# Arduino-Pro-Mini.net
KiCad netlist of a schematic drawn in EAGLE
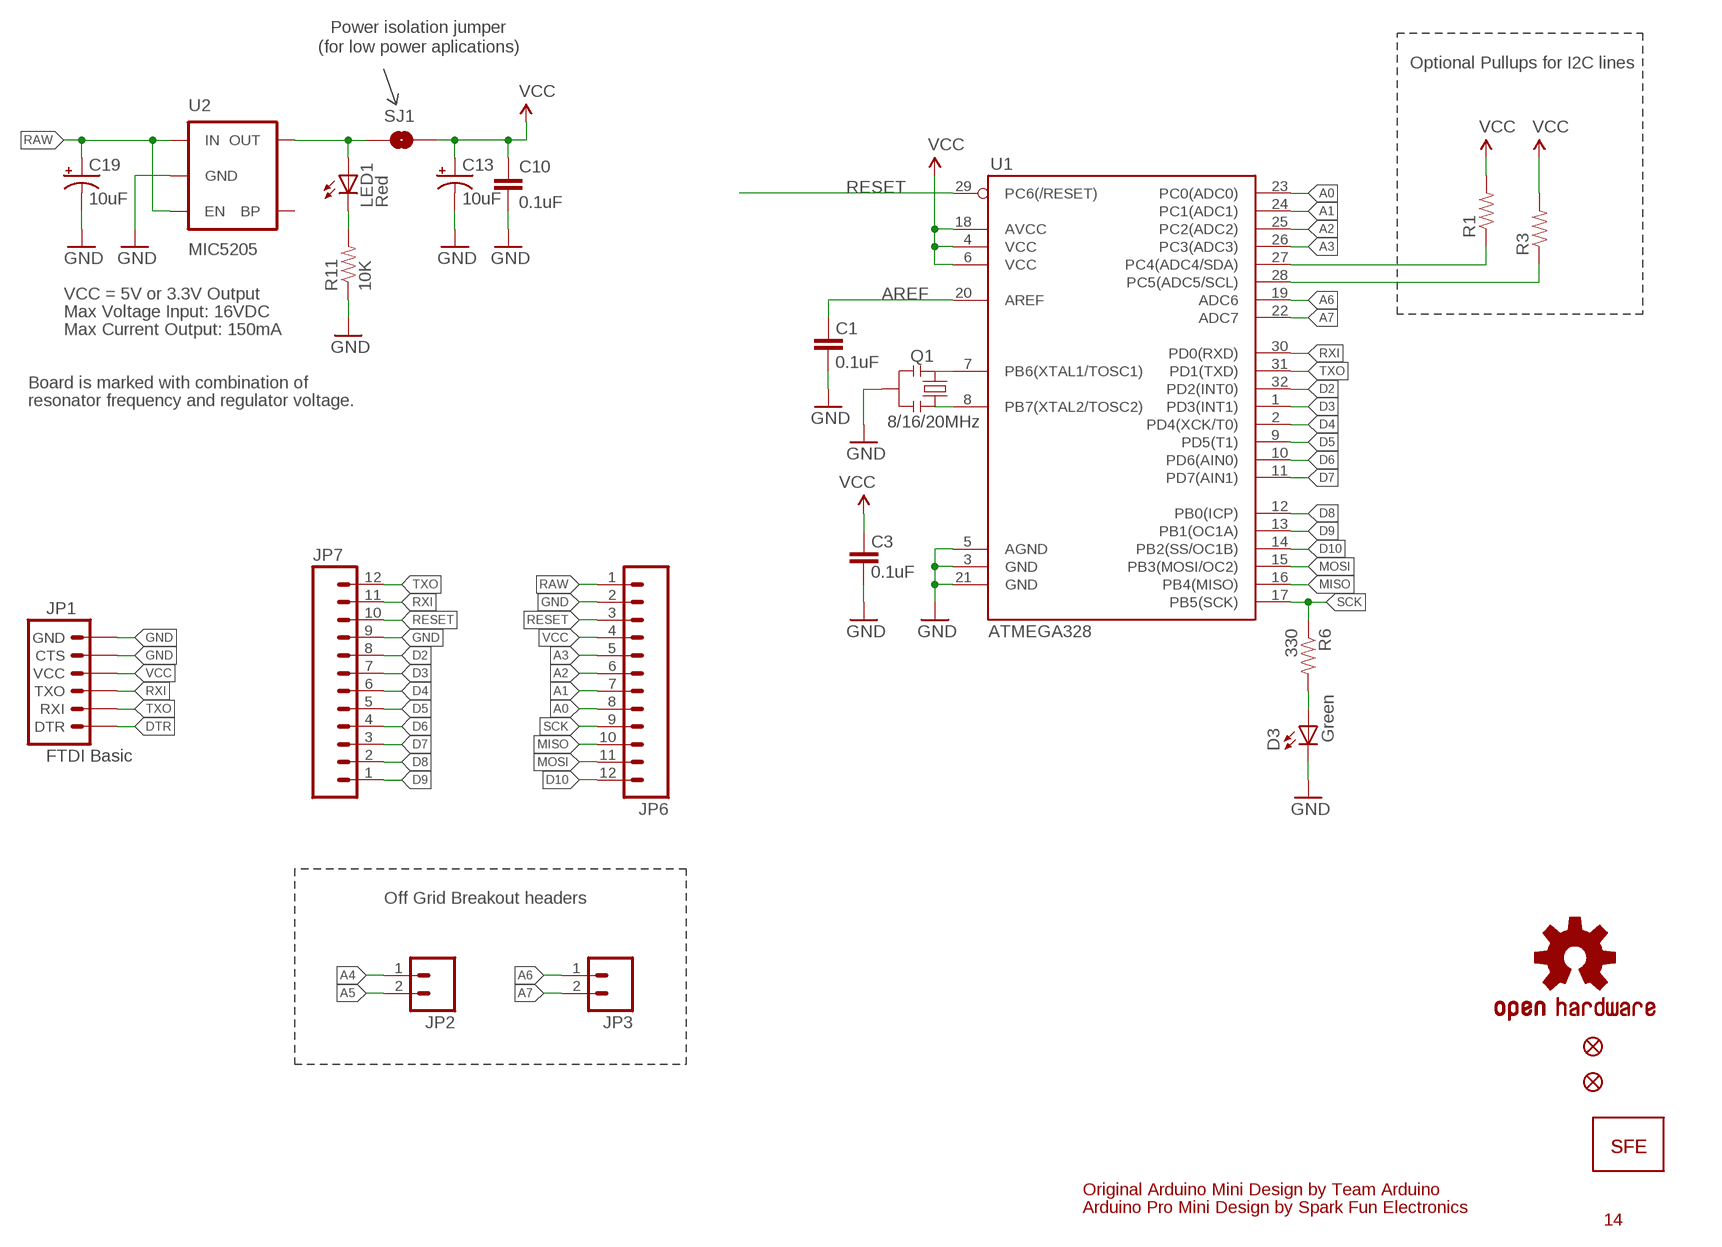
[diagram p0: schematic, sheet 1]

(export (version "E")
  (design (tool "Eeschema 10.0.6"))
  (components
    (comp (ref "C1")
      (value "0.1uF")
      (footprint "eagle-import:0603-CAP")
      (libsource (lib "eagle-import") (part "CAP0603-CAP"))
    )
    (comp (ref "C3")
      (value "0.1uF")
      (footprint "eagle-import:0603-CAP")
      (libsource (lib "eagle-import") (part "CAP0603-CAP"))
    )
    (comp (ref "C10")
      (value "0.1uF")
      (footprint "eagle-import:0603-CAP")
      (libsource (lib "eagle-import") (part "CAP0603-CAP"))
    )
    (comp (ref "C13")
      (value "10uF")
      (footprint "eagle-import:EIA3216")
      (libsource (lib "eagle-import") (part "CAP_POL1206"))
    )
    (comp (ref "C19")
      (value "10uF")
      (footprint "eagle-import:EIA3216")
      (libsource (lib "eagle-import") (part "CAP_POL1206"))
    )
    (comp (ref "D3")
      (value "Green")
      (footprint "eagle-import:0603-LED-ALT1")
      (libsource (lib "eagle-import") (part "LED"))
    )
    (comp (ref "JP1")
      (value "FTDI Basic")
      (footprint "eagle-import:1X06")
      (libsource (lib "eagle-import") (part "ARDUINO_SERIAL_PROGRAMPTH"))
    )
    (comp (ref "JP2")
      (value "M02PTH")
      (footprint "eagle-import:1X02")
      (libsource (lib "eagle-import") (part "M02PTH"))
    )
    (comp (ref "JP3")
      (value "M02PTH")
      (footprint "eagle-import:1X02")
      (libsource (lib "eagle-import") (part "M02PTH"))
    )
    (comp (ref "JP5")
      (value "FIDUCIALUFIDUCIAL")
      (footprint "eagle-import:MICRO-FIDUCIAL")
      (libsource (lib "eagle-import") (part "FIDUCIALUFIDUCIAL"))
    )
    (comp (ref "JP6")
      (value "M12PTH")
      (footprint "eagle-import:1X12")
      (libsource (lib "eagle-import") (part "M12PTH"))
    )
    (comp (ref "JP7")
      (value "M12PTH")
      (footprint "eagle-import:1X12")
      (libsource (lib "eagle-import") (part "M12PTH"))
    )
    (comp (ref "JP8")
      (value "FIDUCIALUFIDUCIAL")
      (footprint "eagle-import:MICRO-FIDUCIAL")
      (libsource (lib "eagle-import") (part "FIDUCIALUFIDUCIAL"))
    )
    (comp (ref "LED1")
      (value "Red")
      (footprint "eagle-import:0603-LED-ALT1")
      (libsource (lib "eagle-import") (part "LED"))
    )
    (comp (ref "Q1")
      (value "8/16/20MHz")
      (footprint "eagle-import:RESONATOR-SMD-1_1")
      (libsource (lib "eagle-import") (part "RESONATOR1{colon}1"))
    )
    (comp (ref "R1")
      (value "RESISTOR0603-RES")
      (footprint "eagle-import:0603-RES")
      (libsource (lib "eagle-import") (part "RESISTOR0603-RES"))
    )
    (comp (ref "R3")
      (value "RESISTOR0603-RES")
      (footprint "eagle-import:0603-RES")
      (libsource (lib "eagle-import") (part "RESISTOR0603-RES"))
    )
    (comp (ref "R6")
      (value "330")
      (footprint "eagle-import:0603-RES")
      (libsource (lib "eagle-import") (part "RESISTOR0603-RES"))
    )
    (comp (ref "R11")
      (value "10K")
      (footprint "eagle-import:0603-RES")
      (libsource (lib "eagle-import") (part "RESISTOR0603-RES"))
    )
    (comp (ref "SJ1")
      (value "SOLDERJUMPERNC")
      (footprint "eagle-import:SJ_2S")
      (libsource (lib "eagle-import") (part "SOLDERJUMPERNC"))
    )
    (comp (ref "U$1")
      (value "LOGO-SFESK")
      (footprint "eagle-import:SFE-LOGO-FLAME")
      (libsource (lib "eagle-import") (part "LOGO-SFESK"))
    )
    (comp (ref "U$3")
      (value "OSHW-LOGOS")
      (footprint "eagle-import:OSHW-LOGO-S")
      (libsource (lib "eagle-import") (part "OSHW-LOGOS"))
    )
    (comp (ref "U$11")
      (value "LOGO-SFENEW")
      (footprint "eagle-import:SFE-NEW-WEBLOGO")
      (libsource (lib "eagle-import") (part "LOGO-SFENEW"))
    )
    (comp (ref "U1")
      (value "ATMEGA328")
      (footprint "eagle-import:TQFP32-08")
      (libsource (lib "eagle-import") (part "ATMEGA168"))
    )
    (comp (ref "U2")
      (value "MIC5205")
      (footprint "eagle-import:SOT23-5")
      (libsource (lib "eagle-import") (part "V_REG_LDOSMD"))
    )
  )
  (nets
    (net (code "1") (name "/AREF") (class "Default")
      (node (ref "C1") (pin "2") (pinfunction "2_2") (pintype "passive"))
      (node (ref "U1") (pin "20") (pinfunction "AREF_20") (pintype "bidirectional"))
    )
    (net (code "2") (name "A0") (class "Default")
      (node (ref "JP6") (pin "8") (pinfunction "8_8") (pintype "passive"))
      (node (ref "U1") (pin "23") (pinfunction "PC0(ADC0)_23") (pintype "bidirectional"))
    )
    (net (code "3") (name "A1") (class "Default")
      (node (ref "JP6") (pin "7") (pinfunction "7_7") (pintype "passive"))
      (node (ref "U1") (pin "24") (pinfunction "PC1(ADC1)_24") (pintype "bidirectional"))
    )
    (net (code "4") (name "A2") (class "Default")
      (node (ref "JP6") (pin "6") (pinfunction "6_6") (pintype "passive"))
      (node (ref "U1") (pin "25") (pinfunction "PC2(ADC2)_25") (pintype "bidirectional"))
    )
    (net (code "5") (name "A3") (class "Default")
      (node (ref "JP6") (pin "5") (pinfunction "5_5") (pintype "passive"))
      (node (ref "U1") (pin "26") (pinfunction "PC3(ADC3)_26") (pintype "bidirectional"))
    )
    (net (code "6") (name "A4") (class "Default")
      (node (ref "JP2") (pin "1") (pinfunction "1_1") (pintype "passive"))
      (node (ref "R1") (pin "1") (pinfunction "1_1") (pintype "passive"))
      (node (ref "U1") (pin "27") (pinfunction "PC4(ADC4/SDA)_27") (pintype "bidirectional"))
    )
    (net (code "7") (name "A5") (class "Default")
      (node (ref "JP2") (pin "2") (pinfunction "2_2") (pintype "passive"))
      (node (ref "R3") (pin "1") (pinfunction "1_1") (pintype "passive"))
      (node (ref "U1") (pin "28") (pinfunction "PC5(ADC5/SCL)_28") (pintype "bidirectional"))
    )
    (net (code "8") (name "A6") (class "Default")
      (node (ref "JP3") (pin "1") (pinfunction "1_1") (pintype "passive"))
      (node (ref "U1") (pin "19") (pinfunction "ADC6_19") (pintype "bidirectional"))
    )
    (net (code "9") (name "A7") (class "Default")
      (node (ref "JP3") (pin "2") (pinfunction "2_2") (pintype "passive"))
      (node (ref "U1") (pin "22") (pinfunction "ADC7_22") (pintype "bidirectional"))
    )
    (net (code "10") (name "D2") (class "Default")
      (node (ref "JP7") (pin "8") (pinfunction "8_8") (pintype "passive"))
      (node (ref "U1") (pin "32") (pinfunction "PD2(INT0)_32") (pintype "bidirectional"))
    )
    (net (code "11") (name "D3") (class "Default")
      (node (ref "JP7") (pin "7") (pinfunction "7_7") (pintype "passive"))
      (node (ref "U1") (pin "1") (pinfunction "PD3(INT1)_1") (pintype "bidirectional"))
    )
    (net (code "12") (name "D4") (class "Default")
      (node (ref "JP7") (pin "6") (pinfunction "6_6") (pintype "passive"))
      (node (ref "U1") (pin "2") (pinfunction "PD4(XCK/T0)_2") (pintype "bidirectional"))
    )
    (net (code "13") (name "D5") (class "Default")
      (node (ref "JP7") (pin "5") (pinfunction "5_5") (pintype "passive"))
      (node (ref "U1") (pin "9") (pinfunction "PD5(T1)_9") (pintype "bidirectional"))
    )
    (net (code "14") (name "D6") (class "Default")
      (node (ref "JP7") (pin "4") (pinfunction "4_4") (pintype "passive"))
      (node (ref "U1") (pin "10") (pinfunction "PD6(AIN0)_10") (pintype "bidirectional"))
    )
    (net (code "15") (name "D7") (class "Default")
      (node (ref "JP7") (pin "3") (pinfunction "3_3") (pintype "passive"))
      (node (ref "U1") (pin "11") (pinfunction "PD7(AIN1)_11") (pintype "bidirectional"))
    )
    (net (code "16") (name "D8") (class "Default")
      (node (ref "JP7") (pin "2") (pinfunction "2_2") (pintype "passive"))
      (node (ref "U1") (pin "12") (pinfunction "PB0(ICP)_12") (pintype "bidirectional"))
    )
    (net (code "17") (name "D9") (class "Default")
      (node (ref "JP7") (pin "1") (pinfunction "1_1") (pintype "passive"))
      (node (ref "U1") (pin "13") (pinfunction "PB1(OC1A)_13") (pintype "bidirectional"))
    )
    (net (code "18") (name "D10") (class "Default")
      (node (ref "JP6") (pin "12") (pinfunction "12_12") (pintype "passive"))
      (node (ref "U1") (pin "14") (pinfunction "PB2(SS/OC1B)_14") (pintype "bidirectional"))
    )
    (net (code "19") (name "DTR") (class "Default")
      (node (ref "JP1") (pin "1") (pinfunction "DTR_1") (pintype "passive"))
    )
    (net (code "20") (name "GND") (class "Default")
      (node (ref "C1") (pin "1") (pinfunction "1_1") (pintype "passive"))
      (node (ref "C10") (pin "2") (pinfunction "2_2") (pintype "passive"))
      (node (ref "C13") (pin "C") (pinfunction "-_C") (pintype "passive"))
      (node (ref "C19") (pin "C") (pinfunction "-_C") (pintype "passive"))
      (node (ref "C3") (pin "1") (pinfunction "1_1") (pintype "passive"))
      (node (ref "D3") (pin "C") (pinfunction "C_C") (pintype "passive"))
      (node (ref "JP1") (pin "5") (pinfunction "CTS_5") (pintype "passive"))
      (node (ref "JP1") (pin "6") (pinfunction "GND_6") (pintype "passive"))
      (node (ref "JP6") (pin "2") (pinfunction "2_2") (pintype "passive"))
      (node (ref "JP7") (pin "9") (pinfunction "9_9") (pintype "passive"))
      (node (ref "Q1") (pin "2") (pinfunction "2_2") (pintype "passive"))
      (node (ref "R11") (pin "1") (pinfunction "1_1") (pintype "passive"))
      (node (ref "U1") (pin "21") (pinfunction "GND_21") (pintype "bidirectional"))
      (node (ref "U1") (pin "3") (pinfunction "GND_3") (pintype "bidirectional"))
      (node (ref "U1") (pin "5") (pinfunction "AGND_5") (pintype "bidirectional"))
      (node (ref "U2") (pin "2") (pinfunction "GND_2") (pintype "input"))
    )
    (net (code "21") (name "MISO") (class "Default")
      (node (ref "JP6") (pin "10") (pinfunction "10_10") (pintype "passive"))
      (node (ref "U1") (pin "16") (pinfunction "PB4(MISO)_16") (pintype "bidirectional"))
    )
    (net (code "22") (name "MOSI") (class "Default")
      (node (ref "JP6") (pin "11") (pinfunction "11_11") (pintype "passive"))
      (node (ref "U1") (pin "15") (pinfunction "PB3(MOSI/OC2)_15") (pintype "bidirectional"))
    )
    (net (code "23") (name "Net-(D3-PadA)") (class "Default")
      (node (ref "D3") (pin "A") (pinfunction "A_A") (pintype "passive"))
      (node (ref "R6") (pin "2") (pinfunction "2_2") (pintype "passive"))
    )
    (net (code "24") (name "Net-(LED1-PadC)") (class "Default")
      (node (ref "LED1") (pin "C") (pinfunction "C_C") (pintype "passive"))
      (node (ref "R11") (pin "2") (pinfunction "2_2") (pintype "passive"))
    )
    (net (code "25") (name "Net-(U1-PB6(XTAL1{slash}TOSC1))") (class "Default")
      (node (ref "Q1") (pin "1") (pinfunction "1_1") (pintype "passive"))
      (node (ref "U1") (pin "7") (pinfunction "PB6(XTAL1/TOSC1)_7") (pintype "bidirectional"))
    )
    (net (code "26") (name "Net-(U1-PB7(XTAL2{slash}TOSC2))") (class "Default")
      (node (ref "Q1") (pin "3") (pinfunction "3_3") (pintype "passive"))
      (node (ref "U1") (pin "8") (pinfunction "PB7(XTAL2/TOSC2)_8") (pintype "bidirectional"))
    )
    (net (code "27") (name "Net-(U2-OUT)") (class "Default")
      (node (ref "LED1") (pin "A") (pinfunction "A_A") (pintype "passive"))
      (node (ref "SJ1") (pin "1") (pinfunction "1_1") (pintype "passive"))
      (node (ref "U2") (pin "5") (pinfunction "OUT_5") (pintype "passive"))
    )
    (net (code "28") (name "RAW") (class "Default")
      (node (ref "C19") (pin "A") (pinfunction "+_A") (pintype "passive"))
      (node (ref "JP6") (pin "1") (pinfunction "1_1") (pintype "passive"))
      (node (ref "U2") (pin "1") (pinfunction "IN_1") (pintype "input"))
      (node (ref "U2") (pin "3") (pinfunction "EN_3") (pintype "input"))
    )
    (net (code "29") (name "RESET") (class "Default")
      (node (ref "JP6") (pin "3") (pinfunction "3_3") (pintype "passive"))
      (node (ref "JP7") (pin "10") (pinfunction "10_10") (pintype "passive"))
      (node (ref "U1") (pin "29") (pinfunction "PC6(/RESET)_29") (pintype "bidirectional"))
    )
    (net (code "30") (name "RXI") (class "Default")
      (node (ref "JP1") (pin "3") (pinfunction "TXO_3") (pintype "passive"))
      (node (ref "JP7") (pin "11") (pinfunction "11_11") (pintype "passive"))
      (node (ref "U1") (pin "30") (pinfunction "PD0(RXD)_30") (pintype "bidirectional"))
    )
    (net (code "31") (name "SCK") (class "Default")
      (node (ref "JP6") (pin "9") (pinfunction "9_9") (pintype "passive"))
      (node (ref "R6") (pin "1") (pinfunction "1_1") (pintype "passive"))
      (node (ref "U1") (pin "17") (pinfunction "PB5(SCK)_17") (pintype "bidirectional"))
    )
    (net (code "32") (name "TXO") (class "Default")
      (node (ref "JP1") (pin "2") (pinfunction "RXI_2") (pintype "passive"))
      (node (ref "JP7") (pin "12") (pinfunction "12_12") (pintype "passive"))
      (node (ref "U1") (pin "31") (pinfunction "PD1(TXD)_31") (pintype "bidirectional"))
    )
    (net (code "33") (name "VCC") (class "Default")
      (node (ref "C10") (pin "1") (pinfunction "1_1") (pintype "passive"))
      (node (ref "C13") (pin "A") (pinfunction "+_A") (pintype "passive"))
      (node (ref "C3") (pin "2") (pinfunction "2_2") (pintype "passive"))
      (node (ref "JP1") (pin "4") (pinfunction "VCC_4") (pintype "passive"))
      (node (ref "JP6") (pin "4") (pinfunction "4_4") (pintype "passive"))
      (node (ref "R1") (pin "2") (pinfunction "2_2") (pintype "passive"))
      (node (ref "R3") (pin "2") (pinfunction "2_2") (pintype "passive"))
      (node (ref "SJ1") (pin "2") (pinfunction "2_2") (pintype "passive"))
      (node (ref "U1") (pin "18") (pinfunction "AVCC_18") (pintype "bidirectional"))
      (node (ref "U1") (pin "4") (pinfunction "VCC_4") (pintype "bidirectional"))
      (node (ref "U1") (pin "6") (pinfunction "VCC_6") (pintype "bidirectional"))
    )
    (net (code "34") (name "unconnected-(U2-BP-Pad4)") (class "Default")
      (node (ref "U2") (pin "4") (pinfunction "BP_4") (pintype "input"))
    )
  )
)
